# fuelgauge.net
KiCad netlist of a schematic drawn in Altium Designer
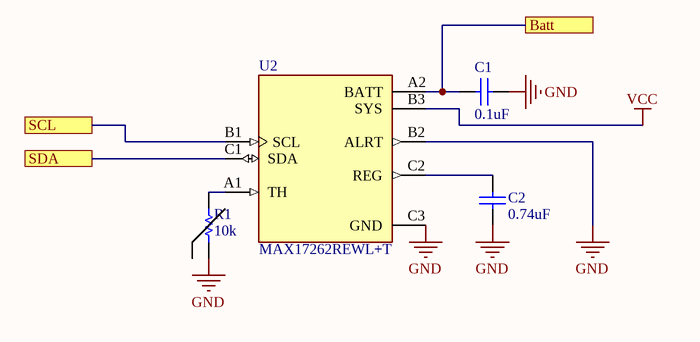
[diagram p0: fuelgauge.SchDoc]

(export (version "E")
  (design (tool "Eeschema 10.0.6"))
  (components
    (comp (ref "C1")
      (value "0.1uF")
      (description "Capacitor")
      (libsource (lib "Simulation Generic Components") (part "Capacitor"))
    )
    (comp (ref "C2")
      (value "0.74uF")
      (description "Capacitor")
      (libsource (lib "Simulation Generic Components") (part "Capacitor"))
    )
    (comp (ref "R1")
      (value "10k")
      (description "Resistor")
      (libsource (lib "Simulation Generic Components") (part "Resistor"))
    )
    (comp (ref "U2")
      (value "MAX17262REWL+T")
      (footprint "AD 9-WLP")
      (description "Battery Fuel Gauge IC LiFePO4/Li-ion 9-WLP (1.47x1.45)")
      (libsource (lib "LIB2022 - ICs") (part "MAX17262REWL+T"))
    )
  )
  (nets
    (net (code "1") (name "/Batt") (class "Default")
      (node (ref "C1") (pin "1") (pinfunction "1_1") (pintype "passive"))
      (node (ref "U2") (pin "A2") (pinfunction "BATT_A2") (pintype "power_in"))
    )
    (net (code "2") (name "/SCL") (class "Default")
      (node (ref "U2") (pin "B1") (pinfunction "SCL_B1") (pintype "input"))
    )
    (net (code "3") (name "/SDA") (class "Default")
      (node (ref "U2") (pin "C1") (pinfunction "SDA_C1") (pintype "bidirectional"))
    )
    (net (code "4") (name "GND") (class "Default")
      (node (ref "C1") (pin "2") (pinfunction "2_2") (pintype "passive"))
      (node (ref "C2") (pin "1") (pinfunction "1_1") (pintype "passive"))
      (node (ref "R1") (pin "1") (pinfunction "1_1") (pintype "passive"))
      (node (ref "U2") (pin "B2") (pinfunction "ALRT_B2") (pintype "output"))
      (node (ref "U2") (pin "C3") (pinfunction "GND_C3") (pintype "power_in"))
    )
    (net (code "5") (name "Net-(U2-REG)") (class "Default")
      (node (ref "C2") (pin "2") (pinfunction "2_2") (pintype "passive"))
      (node (ref "U2") (pin "C2") (pinfunction "REG_C2") (pintype "output"))
    )
    (net (code "6") (name "Net-(U2-TH)") (class "Default")
      (node (ref "R1") (pin "2") (pinfunction "2_2") (pintype "passive"))
      (node (ref "U2") (pin "A1") (pinfunction "TH_A1") (pintype "input"))
    )
    (net (code "7") (name "VCC") (class "Default")
      (node (ref "U2") (pin "B3") (pinfunction "SYS_B3") (pintype "power_in"))
    )
  )
)
